# tx_path.net
KiCad netlist of a schematic drawn in Altium Designer
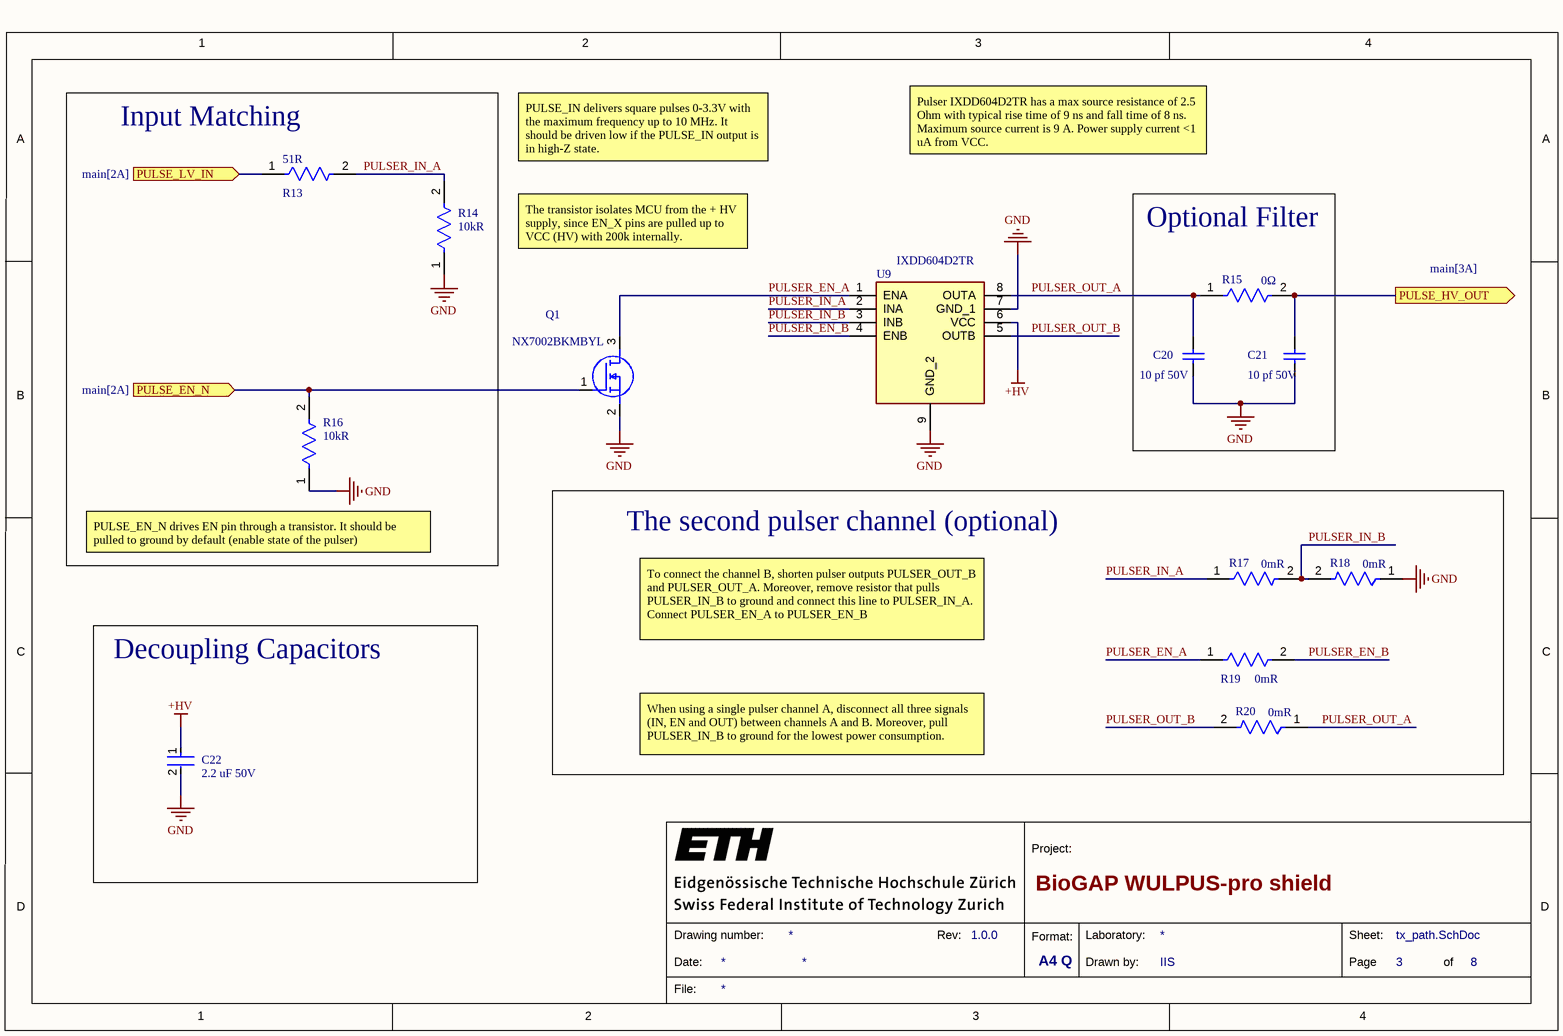
[diagram p0: tx_path.SchDoc]

(export (version "E")
  (design (tool "Eeschema 10.0.6"))
  (components
    (comp (ref "C20")
      (value "GRM1555C1H100JA01D")
      (footprint "CAPC1005X55X25LL05T10")
      (fields (field (name "MANUFACTURER") "Murata") (field (name "CAPACITANCE") "10 pf 50V"))
      (libsource (lib "Altium Content Vault") (part "CAP"))
    )
    (comp (ref "C21")
      (value "GRM1555C1H100JA01D")
      (footprint "CAPC1005X55X25LL05T10")
      (fields (field (name "MANUFACTURER") "Murata") (field (name "CAPACITANCE") "10 pf 50V"))
      (libsource (lib "Altium Content Vault") (part "CAP"))
    )
    (comp (ref "C22")
      (value "GRM188R61H225ME11D")
      (footprint "FP-GRM188-0_2-IPC_B")
      (fields (field (name "CAPACITANCE") "2.2 uF 50V") (field (name "TOLERANCE") "20%"))
      (libsource (lib "Altium Content Vault") (part "11868f565c42a9108669ba33697ecf6"))
    )
    (comp (ref "Q1")
      (value "NX7002BKMBYL")
      (footprint "SamacSys:NX7002BKMBYL")
      (description "MOSFET (N-Channel)")
      (fields (field (name "MOUSER PART NUMBER") "771-NX7002BKMBYL"))
      (libsource (lib "*") (part "NX7002BKMBYL"))
    )
    (comp (ref "R13")
      (value "CRCW040251R0JNED")
      (footprint "FP-CRCW0402-e3-IPC_C")
      (fields (field (name "TOLERANCE") "5%") (field (name "RESISTANCE") "51R"))
      (libsource (lib "Altium Content Vault") (part "1029c3af85768c4190bb7ad29bc67b5"))
    )
    (comp (ref "R14")
      (value "CRCW040210K0JNED")
      (footprint "FP-CRCW0402-e3-IPC_B")
      (fields (field (name "RESISTANCE") "10kR") (field (name "TOLERANCE") "5%"))
      (libsource (lib "Altium Content Vault") (part "1029c3af85768c4190bb7ad29bc67b5"))
    )
    (comp (ref "R15")
      (value "0Ω")
      (footprint "FP-ERJ-3GEY0R00V-MFG")
      (description "ERJ-3GEY0R00V")
      (fields (field (name "TOLERANCE") "5%") (field (name "MANUFACTURER") "Panasonic"))
      (libsource (lib "Altium Content Vault") (part "1029c3af85768c4190bb7ad29bc67b5"))
    )
    (comp (ref "R16")
      (value "CRCW040210K0JNED")
      (footprint "FP-CRCW0402-e3-IPC_B")
      (fields (field (name "RESISTANCE") "10kR") (field (name "TOLERANCE") "5%"))
      (libsource (lib "Altium Content Vault") (part "1029c3af85768c4190bb7ad29bc67b5"))
    )
    (comp (ref "R17")
      (value "CRCW04020000Z0ED")
      (footprint "FP-CRCW0402-e3-IPC_C")
      (fields (field (name "TOLERANCE") "5%") (field (name "RESISTANCE") "0mR"))
      (libsource (lib "Altium Content Vault") (part "1029c3af85768c4190bb7ad29bc67b5"))
    )
    (comp (ref "R18")
      (value "CRCW04020000Z0ED")
      (footprint "FP-CRCW0402-e3-IPC_C")
      (fields (field (name "TOLERANCE") "5%") (field (name "RESISTANCE") "0mR"))
      (libsource (lib "Altium Content Vault") (part "1029c3af85768c4190bb7ad29bc67b5"))
    )
    (comp (ref "R19")
      (value "CRCW04020000Z0ED")
      (footprint "FP-CRCW0402-e3-IPC_C")
      (fields (field (name "TOLERANCE") "5%") (field (name "RESISTANCE") "0mR"))
      (libsource (lib "Altium Content Vault") (part "1029c3af85768c4190bb7ad29bc67b5"))
    )
    (comp (ref "R20")
      (value "CRCW04020000Z0ED")
      (footprint "FP-CRCW0402-e3-IPC_C")
      (fields (field (name "TOLERANCE") "5%") (field (name "RESISTANCE") "0mR"))
      (libsource (lib "Altium Content Vault") (part "1029c3af85768c4190bb7ad29bc67b5"))
    )
    (comp (ref "U9")
      (value "IXDD604D2TR")
      (footprint "SamacSys:SON95P500X400X100-9N")
      (description "Integrated Circuit")
      (fields (field (name "MOUSER PART NUMBER") "849-IXDD604D2TR"))
      (libsource (lib "SamacSys") (part "IXDD604D2TR"))
    )
  )
  (nets
    (net (code "1") (name "+HV") (class "Default")
      (node (ref "C22") (pin "1") (pinfunction "1_1") (pintype "passive"))
      (node (ref "U9") (pin "6") (pinfunction "VCC_6") (pintype "passive"))
    )
    (net (code "3") (name "/PULSER_EN_A") (class "Default")
      (node (ref "Q1") (pin "3") (pinfunction "D_3") (pintype "passive"))
      (node (ref "R19") (pin "1") (pinfunction "1_1") (pintype "passive"))
      (node (ref "U9") (pin "1") (pinfunction "ENA_1") (pintype "passive"))
    )
    (net (code "4") (name "/PULSER_EN_B") (class "Default")
      (node (ref "R19") (pin "2") (pinfunction "2_2") (pintype "passive"))
      (node (ref "U9") (pin "4") (pinfunction "ENB_4") (pintype "passive"))
    )
    (net (code "5") (name "/PULSER_IN_A") (class "Default")
      (node (ref "R13") (pin "2") (pinfunction "2_2") (pintype "passive"))
      (node (ref "R14") (pin "2") (pinfunction "2_2") (pintype "passive"))
      (node (ref "R17") (pin "1") (pinfunction "1_1") (pintype "passive"))
      (node (ref "U9") (pin "2") (pinfunction "INA_2") (pintype "passive"))
    )
    (net (code "6") (name "/PULSER_IN_B") (class "Default")
      (node (ref "R17") (pin "2") (pinfunction "2_2") (pintype "passive"))
      (node (ref "R18") (pin "2") (pinfunction "2_2") (pintype "passive"))
      (node (ref "U9") (pin "3") (pinfunction "INB_3") (pintype "passive"))
    )
    (net (code "7") (name "/PULSER_OUT_A") (class "Default")
      (node (ref "C20") (pin "2") (pinfunction "2_2") (pintype "passive"))
      (node (ref "R15") (pin "1") (pinfunction "1_1") (pintype "passive"))
      (node (ref "R20") (pin "1") (pinfunction "1_1") (pintype "passive"))
      (node (ref "U9") (pin "8") (pinfunction "OUTA_8") (pintype "passive"))
    )
    (net (code "8") (name "/PULSER_OUT_B") (class "Default")
      (node (ref "R20") (pin "2") (pinfunction "2_2") (pintype "passive"))
      (node (ref "U9") (pin "5") (pinfunction "OUTB_5") (pintype "passive"))
    )
    (net (code "9") (name "/PULSE_EN_N") (class "Default")
      (node (ref "Q1") (pin "1") (pinfunction "G_1") (pintype "passive"))
      (node (ref "R16") (pin "2") (pinfunction "2_2") (pintype "passive"))
    )
    (net (code "10") (name "/PULSE_HV_OUT") (class "Default")
      (node (ref "C21") (pin "2") (pinfunction "2_2") (pintype "passive"))
      (node (ref "R15") (pin "2") (pinfunction "2_2") (pintype "passive"))
    )
    (net (code "11") (name "/PULSE_LV_IN") (class "Default")
      (node (ref "R13") (pin "1") (pinfunction "1_1") (pintype "passive"))
    )
    (net (code "12") (name "GND") (class "Default")
      (node (ref "C20") (pin "1") (pinfunction "1_1") (pintype "passive"))
      (node (ref "C21") (pin "1") (pinfunction "1_1") (pintype "passive"))
      (node (ref "C22") (pin "2") (pinfunction "2_2") (pintype "passive"))
      (node (ref "Q1") (pin "2") (pinfunction "S_2") (pintype "passive"))
      (node (ref "R14") (pin "1") (pinfunction "1_1") (pintype "passive"))
      (node (ref "R16") (pin "1") (pinfunction "1_1") (pintype "passive"))
      (node (ref "R18") (pin "1") (pinfunction "1_1") (pintype "passive"))
      (node (ref "U9") (pin "7") (pinfunction "GND_1_7") (pintype "passive"))
      (node (ref "U9") (pin "9") (pinfunction "GND_2_9") (pintype "passive"))
    )
  )
)
